# LEDs.net
KiCad netlist of a schematic drawn in Altium Designer
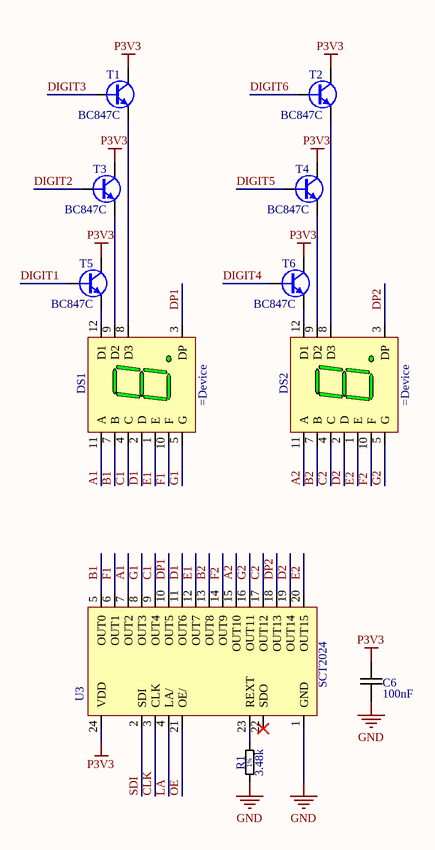
[diagram p0: LEDs.SchDoc]

(export (version "E")
  (design (tool "Eeschema 10.0.6"))
  (components
    (comp (ref "C6")
      (value "100nF")
      (footprint "CAPC0402X60N")
      (description "Non-polarised capacitor")
      (fields
        (field (name "MANUFACTURER") "GENERIC")
        (field (name "MANUFACTURER PART NUMBER") "CC0402_100NF_16V_10%_X7R")
        (field (name "AUTHOR") "KB")
      )
      (libsource (lib "Capacitors") (part "Capacitor - non polarized"))
    )
    (comp (ref "DS1")
      (value "~")
      (footprint "7seg_3digits")
      (description "7-seg LED Display; 9.14mm; 0.36ˇ¨; 3 Digits; Green")
      (fields
        (field (name "MANUFACTURER") "Generic")
        (field (name "MANUFACTURER 1 PART NUMBER") "LTD036BAG-101A-02")
        (field (name "AUTHOR") "JK")
      )
      (libsource (lib "ICs And Semiconductors") (part "7-Segment Green Display CA 3-Digits"))
    )
    (comp (ref "DS2")
      (value "~")
      (footprint "7seg_3digits")
      (description "7-seg LED Display; 9.14mm; 0.36ˇ¨; 3 Digits; Green")
      (fields
        (field (name "MANUFACTURER") "Generic")
        (field (name "MANUFACTURER 1 PART NUMBER") "LTD036BAG-101A-02")
        (field (name "AUTHOR") "JK")
      )
      (libsource (lib "ICs And Semiconductors") (part "7-Segment Green Display CA 3-Digits"))
    )
    (comp (ref "R1")
      (value "3.48k")
      (footprint "RESC0402X40N")
      (description "General Purpose Thick Film Chip Resistor")
      (fields
        (field (name "MANUFACTURER") "GENERIC")
        (field (name "MANUFACTURER PART NUMBER") "R0402_3K48_0.0625W 0.1W 0.125W 0.25W 0.5W 1W 0.75W 1W_100PPM")
        (field (name "AUTHOR") "KB")
      )
      (libsource (lib "Resistors") (part "Resistor - 1%"))
    )
    (comp (ref "T1")
      (value "BC847C")
      (footprint "SOT23-3")
      (description "NPN Bipolar Transistor, 45V, 100mA, 250mW, SOT23")
      (fields (field (name "MANUFACTURER 1 PART NUMBER") "BC847C.215") (field (name "AUTHOR") "KB"))
      (libsource (lib "ICs And Semiconductors") (part "NPN B1 E2 C3"))
    )
    (comp (ref "T2")
      (value "BC847C")
      (footprint "SOT23-3")
      (description "NPN Bipolar Transistor, 45V, 100mA, 250mW, SOT23")
      (fields (field (name "MANUFACTURER 1 PART NUMBER") "BC847C.215") (field (name "AUTHOR") "KB"))
      (libsource (lib "ICs And Semiconductors") (part "NPN B1 E2 C3"))
    )
    (comp (ref "T3")
      (value "BC847C")
      (footprint "SOT23-3")
      (description "NPN Bipolar Transistor, 45V, 100mA, 250mW, SOT23")
      (fields (field (name "MANUFACTURER 1 PART NUMBER") "BC847C.215") (field (name "AUTHOR") "KB"))
      (libsource (lib "ICs And Semiconductors") (part "NPN B1 E2 C3"))
    )
    (comp (ref "T4")
      (value "BC847C")
      (footprint "SOT23-3")
      (description "NPN Bipolar Transistor, 45V, 100mA, 250mW, SOT23")
      (fields (field (name "MANUFACTURER 1 PART NUMBER") "BC847C.215") (field (name "AUTHOR") "KB"))
      (libsource (lib "ICs And Semiconductors") (part "NPN B1 E2 C3"))
    )
    (comp (ref "T5")
      (value "BC847C")
      (footprint "SOT23-3")
      (description "NPN Bipolar Transistor, 45V, 100mA, 250mW, SOT23")
      (fields (field (name "MANUFACTURER 1 PART NUMBER") "BC847C.215") (field (name "AUTHOR") "KB"))
      (libsource (lib "ICs And Semiconductors") (part "NPN B1 E2 C3"))
    )
    (comp (ref "T6")
      (value "BC847C")
      (footprint "SOT23-3")
      (description "NPN Bipolar Transistor, 45V, 100mA, 250mW, SOT23")
      (fields (field (name "MANUFACTURER 1 PART NUMBER") "BC847C.215") (field (name "AUTHOR") "KB"))
      (libsource (lib "ICs And Semiconductors") (part "NPN B1 E2 C3"))
    )
    (comp (ref "U3")
      (value "SCT2024")
      (footprint "SOP-24_N")
      (description "Driver, kontroler LED, 5ˇĹ0mA, Kanały: 16, 3ˇĹ,5V, SOP24")
      (fields
        (field (name "MANUFACTURER") "Generic")
        (field (name "MANUFACTURER 1 PART NUMBER") "SCT2024CSOG")
        (field (name "AUTHOR") "UN")
      )
      (libsource (lib "ICs And Semiconductors") (part "SCT2024"))
    )
  )
  (nets
    (net (code "1") (name "/A1") (class "Default")
      (node (ref "DS1") (pin "11") (pinfunction "A_11") (pintype "passive"))
      (node (ref "U3") (pin "7") (pinfunction "OUT2_7") (pintype "passive"))
    )
    (net (code "2") (name "/A2") (class "Default")
      (node (ref "DS2") (pin "11") (pinfunction "A_11") (pintype "passive"))
      (node (ref "U3") (pin "15") (pinfunction "OUT10_15") (pintype "passive"))
    )
    (net (code "3") (name "/B1") (class "Default")
      (node (ref "DS1") (pin "7") (pinfunction "B_7") (pintype "passive"))
      (node (ref "U3") (pin "5") (pinfunction "OUT0_5") (pintype "passive"))
    )
    (net (code "4") (name "/B2") (class "Default")
      (node (ref "DS2") (pin "7") (pinfunction "B_7") (pintype "passive"))
      (node (ref "U3") (pin "13") (pinfunction "OUT8_13") (pintype "passive"))
    )
    (net (code "5") (name "/C1") (class "Default")
      (node (ref "DS1") (pin "4") (pinfunction "C_4") (pintype "passive"))
      (node (ref "U3") (pin "9") (pinfunction "OUT4_9") (pintype "passive"))
    )
    (net (code "6") (name "/C2") (class "Default")
      (node (ref "DS2") (pin "4") (pinfunction "C_4") (pintype "passive"))
      (node (ref "U3") (pin "17") (pinfunction "OUT12_17") (pintype "passive"))
    )
    (net (code "7") (name "/CLK") (class "Default")
      (node (ref "U3") (pin "3") (pinfunction "CLK_3") (pintype "passive"))
    )
    (net (code "8") (name "/D1") (class "Default")
      (node (ref "DS1") (pin "2") (pinfunction "D_2") (pintype "passive"))
      (node (ref "U3") (pin "11") (pinfunction "OUT6_11") (pintype "passive"))
    )
    (net (code "9") (name "/D2") (class "Default")
      (node (ref "DS2") (pin "2") (pinfunction "D_2") (pintype "passive"))
      (node (ref "U3") (pin "19") (pinfunction "OUT14_19") (pintype "passive"))
    )
    (net (code "10") (name "/DIGIT1") (class "Default")
      (node (ref "T5") (pin "1") (pinfunction "B_1") (pintype "passive"))
    )
    (net (code "11") (name "/DIGIT2") (class "Default")
      (node (ref "T3") (pin "1") (pinfunction "B_1") (pintype "passive"))
    )
    (net (code "12") (name "/DIGIT3") (class "Default")
      (node (ref "T1") (pin "1") (pinfunction "B_1") (pintype "passive"))
    )
    (net (code "13") (name "/DIGIT4") (class "Default")
      (node (ref "T6") (pin "1") (pinfunction "B_1") (pintype "passive"))
    )
    (net (code "14") (name "/DIGIT5") (class "Default")
      (node (ref "T4") (pin "1") (pinfunction "B_1") (pintype "passive"))
    )
    (net (code "15") (name "/DIGIT6") (class "Default")
      (node (ref "T2") (pin "1") (pinfunction "B_1") (pintype "passive"))
    )
    (net (code "16") (name "/DP1") (class "Default")
      (node (ref "DS1") (pin "3") (pinfunction "DP_3") (pintype "passive"))
      (node (ref "U3") (pin "10") (pinfunction "OUT5_10") (pintype "passive"))
    )
    (net (code "17") (name "/DP2") (class "Default")
      (node (ref "DS2") (pin "3") (pinfunction "DP_3") (pintype "passive"))
      (node (ref "U3") (pin "18") (pinfunction "OUT13_18") (pintype "passive"))
    )
    (net (code "18") (name "/E1") (class "Default")
      (node (ref "DS1") (pin "1") (pinfunction "E_1") (pintype "passive"))
      (node (ref "U3") (pin "12") (pinfunction "OUT7_12") (pintype "passive"))
    )
    (net (code "19") (name "/E2") (class "Default")
      (node (ref "DS2") (pin "1") (pinfunction "E_1") (pintype "passive"))
      (node (ref "U3") (pin "20") (pinfunction "OUT15_20") (pintype "passive"))
    )
    (net (code "20") (name "/F1") (class "Default")
      (node (ref "DS1") (pin "10") (pinfunction "F_10") (pintype "passive"))
      (node (ref "U3") (pin "6") (pinfunction "OUT1_6") (pintype "passive"))
    )
    (net (code "21") (name "/F2") (class "Default")
      (node (ref "DS2") (pin "10") (pinfunction "F_10") (pintype "passive"))
      (node (ref "U3") (pin "14") (pinfunction "OUT9_14") (pintype "passive"))
    )
    (net (code "22") (name "/G1") (class "Default")
      (node (ref "DS1") (pin "5") (pinfunction "G_5") (pintype "passive"))
      (node (ref "U3") (pin "8") (pinfunction "OUT3_8") (pintype "passive"))
    )
    (net (code "23") (name "/G2") (class "Default")
      (node (ref "DS2") (pin "5") (pinfunction "G_5") (pintype "passive"))
      (node (ref "U3") (pin "16") (pinfunction "OUT11_16") (pintype "passive"))
    )
    (net (code "24") (name "/LA") (class "Default")
      (node (ref "U3") (pin "4") (pinfunction "LA/_4") (pintype "passive"))
    )
    (net (code "25") (name "/OE") (class "Default")
      (node (ref "U3") (pin "21") (pinfunction "OE/_21") (pintype "passive"))
    )
    (net (code "26") (name "/SDI") (class "Default")
      (node (ref "U3") (pin "2") (pinfunction "SDI_2") (pintype "passive"))
    )
    (net (code "27") (name "GND") (class "Default")
      (node (ref "C6") (pin "1") (pinfunction "1_1") (pintype "passive"))
      (node (ref "R1") (pin "1") (pinfunction "1_1") (pintype "passive"))
      (node (ref "U3") (pin "1") (pinfunction "GND_1") (pintype "power_in"))
    )
    (net (code "28") (name "Net-(DS1-D1)") (class "Default")
      (node (ref "DS1") (pin "12") (pinfunction "D1_12") (pintype "passive"))
      (node (ref "T5") (pin "2") (pinfunction "E_2") (pintype "passive"))
    )
    (net (code "29") (name "Net-(DS1-D2)") (class "Default")
      (node (ref "DS1") (pin "9") (pinfunction "D2_9") (pintype "passive"))
      (node (ref "T3") (pin "2") (pinfunction "E_2") (pintype "passive"))
    )
    (net (code "30") (name "Net-(DS1-D3)") (class "Default")
      (node (ref "DS1") (pin "8") (pinfunction "D3_8") (pintype "passive"))
      (node (ref "T1") (pin "2") (pinfunction "E_2") (pintype "passive"))
    )
    (net (code "31") (name "Net-(DS2-D1)") (class "Default")
      (node (ref "DS2") (pin "12") (pinfunction "D1_12") (pintype "passive"))
      (node (ref "T6") (pin "2") (pinfunction "E_2") (pintype "passive"))
    )
    (net (code "32") (name "Net-(DS2-D2)") (class "Default")
      (node (ref "DS2") (pin "9") (pinfunction "D2_9") (pintype "passive"))
      (node (ref "T4") (pin "2") (pinfunction "E_2") (pintype "passive"))
    )
    (net (code "33") (name "Net-(DS2-D3)") (class "Default")
      (node (ref "DS2") (pin "8") (pinfunction "D3_8") (pintype "passive"))
      (node (ref "T2") (pin "2") (pinfunction "E_2") (pintype "passive"))
    )
    (net (code "34") (name "Net-(U3-REXT)") (class "Default")
      (node (ref "R1") (pin "2") (pinfunction "2_2") (pintype "passive"))
      (node (ref "U3") (pin "23") (pinfunction "REXT_23") (pintype "passive"))
    )
    (net (code "35") (name "P3V3") (class "Default")
      (node (ref "C6") (pin "2") (pinfunction "2_2") (pintype "passive"))
      (node (ref "T1") (pin "3") (pinfunction "C_3") (pintype "passive"))
      (node (ref "T2") (pin "3") (pinfunction "C_3") (pintype "passive"))
      (node (ref "T3") (pin "3") (pinfunction "C_3") (pintype "passive"))
      (node (ref "T4") (pin "3") (pinfunction "C_3") (pintype "passive"))
      (node (ref "T5") (pin "3") (pinfunction "C_3") (pintype "passive"))
      (node (ref "T6") (pin "3") (pinfunction "C_3") (pintype "passive"))
      (node (ref "U3") (pin "24") (pinfunction "VDD_24") (pintype "power_in"))
    )
    (net (code "36") (name "unconnected-(U3-SDO-Pad22)") (class "Default")
      (node (ref "U3") (pin "22") (pinfunction "SDO_22") (pintype "passive+no_connect"))
    )
  )
)
